# 23_Alimentaci_n_Hub.net
KiCad netlist of a schematic drawn in Altium Designer
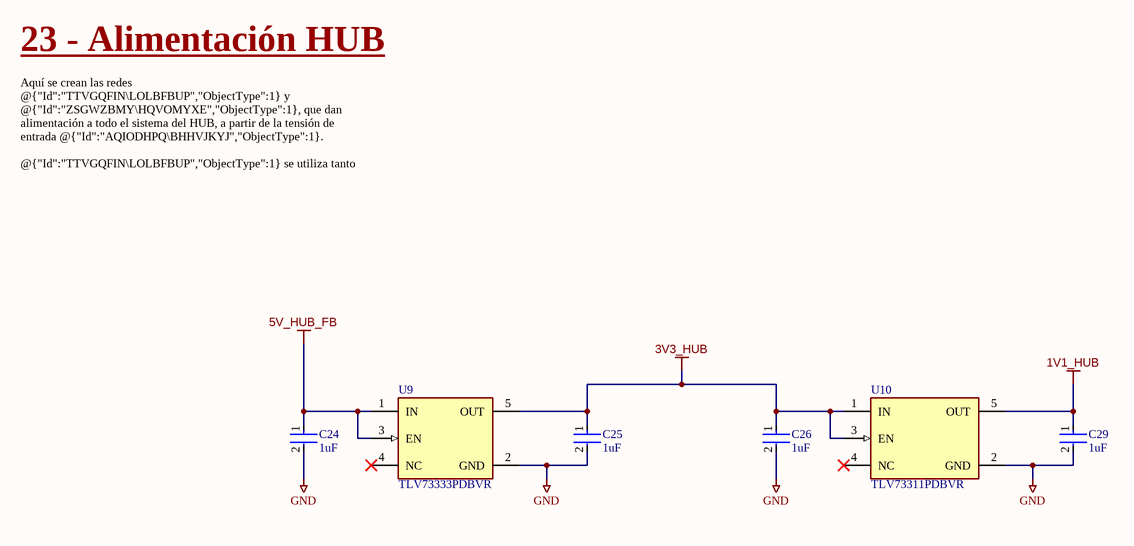
[diagram p0: 23_Alimentación_Hub.SchDoc]

(export (version "E")
  (design (tool "Eeschema 10.0.6"))
  (components
    (comp (ref "C24")
      (value "1uF")
      (footprint "FP-C0402C-BB-IPC_B")
      (description "CAP CER 1UF 16V X5R 0402")
      (fields (field (name "TOLERANCE") "10%"))
      (libsource (lib "Altium Content Vault") (part "b4654b650e69147ec39a6b967a45e02"))
    )
    (comp (ref "C25")
      (value "1uF")
      (footprint "FP-C0402C-BB-IPC_B")
      (description "CAP CER 1UF 16V X5R 0402")
      (fields (field (name "TOLERANCE") "10%"))
      (libsource (lib "Altium Content Vault") (part "b4654b650e69147ec39a6b967a45e02"))
    )
    (comp (ref "C26")
      (value "1uF")
      (footprint "FP-C0402C-BB-IPC_B")
      (description "CAP CER 1UF 16V X5R 0402")
      (fields (field (name "TOLERANCE") "10%"))
      (libsource (lib "Altium Content Vault") (part "b4654b650e69147ec39a6b967a45e02"))
    )
    (comp (ref "C29")
      (value "1uF")
      (footprint "FP-C0402C-BB-IPC_B")
      (description "CAP CER 1UF 16V X5R 0402")
      (fields (field (name "TOLERANCE") "10%"))
      (libsource (lib "Altium Content Vault") (part "b4654b650e69147ec39a6b967a45e02"))
    )
    (comp (ref "U9")
      (value "TLV73333PDBVR")
      (footprint "FP-DBV0005A-MFG")
      (description "IC REG LINEAR 3.3V 300MA SOT23-5")
      (fields
        (field (name "MANUFACTURER") "Texas Instruments")
        (field (name "OCTOPART") "https://octopart.com/tlv73333pdbvr-texas+instruments-51080890")
      )
      (libsource (lib "Altium Content Vault") (part "10cdd6a861ce8db355dac0efc8b397e"))
    )
    (comp (ref "U10")
      (value "TLV73311PDBVR")
      (footprint "FP-DBV0005A-IPC_C")
      (description "IC REG LINEAR 1.1V 300MA SOT23-5")
      (libsource (lib "Altium Content Vault") (part "66ca6db733a9cb813c480efc7723418"))
    )
  )
  (nets
    (net (code "1") (name "1V1_HUB") (class "Default")
      (node (ref "C29") (pin "1") (pinfunction "1_1") (pintype "passive"))
      (node (ref "U10") (pin "5") (pinfunction "OUT_5") (pintype "power_in"))
    )
    (net (code "2") (name "3V3_HUB") (class "Default")
      (node (ref "C25") (pin "1") (pinfunction "1_1") (pintype "passive"))
      (node (ref "C26") (pin "1") (pinfunction "1_1") (pintype "passive"))
      (node (ref "U10") (pin "1") (pinfunction "IN_1") (pintype "power_in"))
      (node (ref "U10") (pin "3") (pinfunction "EN_3") (pintype "input"))
      (node (ref "U9") (pin "5") (pinfunction "OUT_5") (pintype "power_in"))
    )
    (net (code "3") (name "5V_HUB_FB") (class "Default")
      (node (ref "C24") (pin "1") (pinfunction "1_1") (pintype "passive"))
      (node (ref "U9") (pin "1") (pinfunction "IN_1") (pintype "passive"))
      (node (ref "U9") (pin "3") (pinfunction "EN_3") (pintype "input"))
    )
    (net (code "4") (name "GND") (class "Default")
      (node (ref "C24") (pin "2") (pinfunction "2_2") (pintype "passive"))
      (node (ref "C25") (pin "2") (pinfunction "2_2") (pintype "passive"))
      (node (ref "C26") (pin "2") (pinfunction "2_2") (pintype "passive"))
      (node (ref "C29") (pin "2") (pinfunction "2_2") (pintype "passive"))
      (node (ref "U10") (pin "2") (pinfunction "GND_2") (pintype "passive"))
      (node (ref "U9") (pin "2") (pinfunction "GND_2") (pintype "passive"))
    )
    (net (code "5") (name "unconnected-(U9-NC-Pad4)") (class "Default")
      (node (ref "U9") (pin "4") (pinfunction "NC_4") (pintype "passive+no_connect"))
    )
    (net (code "6") (name "unconnected-(U10-NC-Pad4)") (class "Default")
      (node (ref "U10") (pin "4") (pinfunction "NC_4") (pintype "passive+no_connect"))
    )
  )
)
